# LTC3111_buck-boost.net
KiCad netlist of a schematic drawn in EAGLE
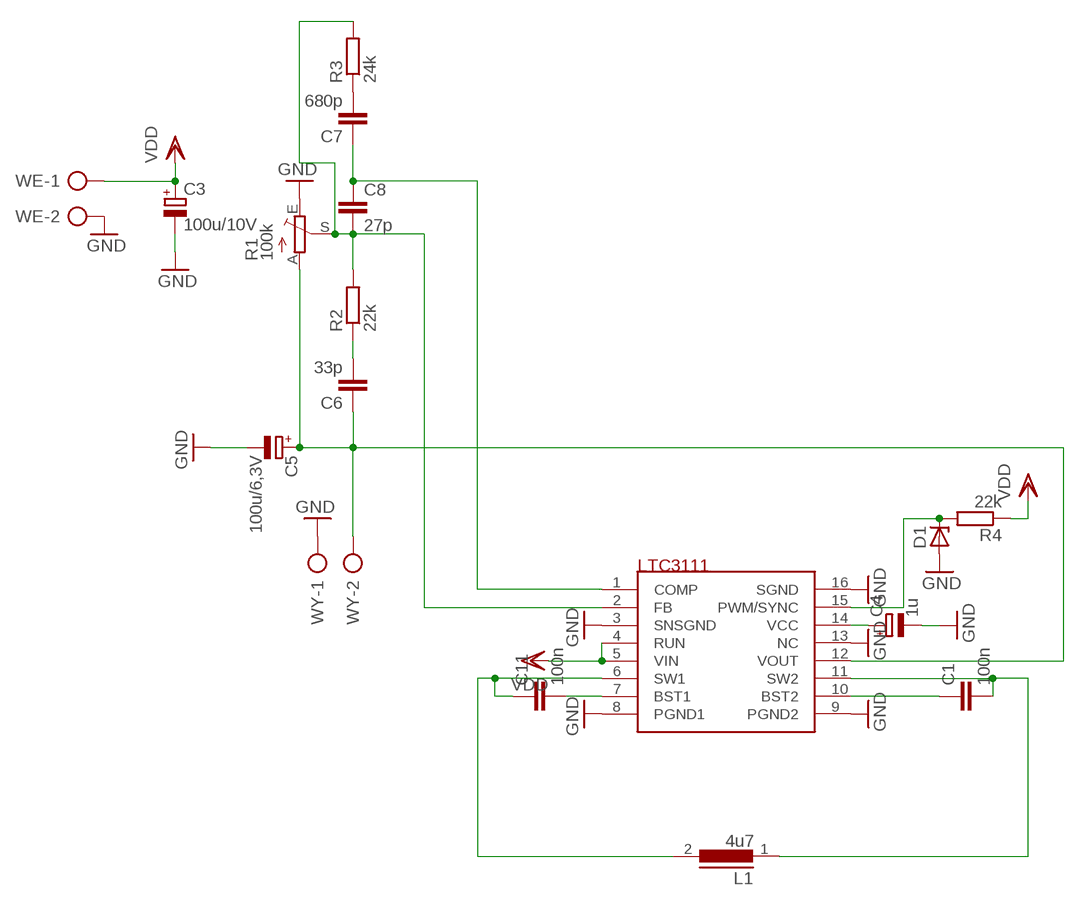
[diagram p0: schematic, sheet 1]

(export (version "E")
  (design (tool "Eeschema 10.0.6"))
  (components
    (comp (ref "C1")
      (value "100n")
      (footprint "eagle-import:C0603K")
      (libsource (lib "eagle-import") (part "C-EUC0603K"))
    )
    (comp (ref "C3")
      (value "100u/10V")
      (footprint "eagle-import:E2,5-6")
      (libsource (lib "eagle-import") (part "CPOL-EUE2.5-6"))
    )
    (comp (ref "C4")
      (value "1u")
      (footprint "eagle-import:E2,5-6")
      (libsource (lib "eagle-import") (part "CPOL-EUE2.5-6"))
    )
    (comp (ref "C5")
      (value "100u/6,3V")
      (footprint "eagle-import:E2,5-7")
      (libsource (lib "eagle-import") (part "CPOL-EUE2.5-7"))
    )
    (comp (ref "C6")
      (value "33p")
      (footprint "eagle-import:C0805")
      (libsource (lib "eagle-import") (part "C-EUC0805"))
    )
    (comp (ref "C7")
      (value "680p")
      (footprint "eagle-import:C0805")
      (libsource (lib "eagle-import") (part "C-EUC0805"))
    )
    (comp (ref "C8")
      (value "27p")
      (footprint "eagle-import:C0805")
      (libsource (lib "eagle-import") (part "C-EUC0805"))
    )
    (comp (ref "C11")
      (value "100n")
      (footprint "eagle-import:C0603K")
      (libsource (lib "eagle-import") (part "C-EUC0603K"))
    )
    (comp (ref "D1")
      (value "ZENER-DIODESOD80C")
      (footprint "eagle-import:SOD80C")
      (libsource (lib "eagle-import") (part "ZENER-DIODESOD80C"))
    )
    (comp (ref "L1")
      (value "4u7")
      (footprint "eagle-import:DR73")
      (libsource (lib "eagle-import") (part "DR73"))
    )
    (comp (ref "R1")
      (value "100k")
      (footprint "eagle-import:RJ9W")
      (libsource (lib "eagle-import") (part "TRIM_EU-RJ9W"))
    )
    (comp (ref "R2")
      (value "22k")
      (footprint "eagle-import:R0805")
      (libsource (lib "eagle-import") (part "R-EU_R0805"))
    )
    (comp (ref "R3")
      (value "24k")
      (footprint "eagle-import:R0805")
      (libsource (lib "eagle-import") (part "R-EU_R0805"))
    )
    (comp (ref "R4")
      (value "22k")
      (footprint "eagle-import:R0805")
      (libsource (lib "eagle-import") (part "R-EU_R0805"))
    )
    (comp (ref "U$2")
      (value "LTC3111")
      (footprint "eagle-import:MSOP16")
      (libsource (lib "eagle-import") (part "LTC3111"))
    )
    (comp (ref "WE")
      (value "AK300/2")
      (footprint "eagle-import:AK300_2")
      (libsource (lib "eagle-import") (part "AK300/2"))
    )
    (comp (ref "WY")
      (value "AK300/2")
      (footprint "eagle-import:AK300_2")
      (libsource (lib "eagle-import") (part "AK300/2"))
    )
  )
  (nets
    (net (code "1") (name "GND") (class "Default")
      (node (ref "C3") (pin "-") (pinfunction "-_-") (pintype "passive"))
      (node (ref "C4") (pin "-") (pinfunction "-_-") (pintype "passive"))
      (node (ref "C5") (pin "-") (pinfunction "-_-") (pintype "passive"))
      (node (ref "D1") (pin "A") (pinfunction "A_A") (pintype "passive"))
      (node (ref "R1") (pin "E") (pinfunction "E_E") (pintype "passive"))
      (node (ref "U$2") (pin "13") (pinfunction "NC_13") (pintype "bidirectional"))
      (node (ref "U$2") (pin "16") (pinfunction "SGND_16") (pintype "bidirectional"))
      (node (ref "U$2") (pin "3") (pinfunction "SNSGND_3") (pintype "bidirectional"))
      (node (ref "U$2") (pin "8") (pinfunction "PGND1_8") (pintype "bidirectional"))
      (node (ref "U$2") (pin "9") (pinfunction "PGND2_9") (pintype "bidirectional"))
      (node (ref "WE") (pin "2") (pinfunction "KL_2") (pintype "passive"))
      (node (ref "WY") (pin "1") (pinfunction "KL_1") (pintype "passive"))
    )
    (net (code "2") (name "Net-(C6-Pad2)") (class "Default")
      (node (ref "C6") (pin "2") (pinfunction "2_2") (pintype "passive"))
      (node (ref "R2") (pin "1") (pinfunction "1_1") (pintype "passive"))
    )
    (net (code "3") (name "Net-(C7-Pad2)") (class "Default")
      (node (ref "C7") (pin "2") (pinfunction "2_2") (pintype "passive"))
      (node (ref "R3") (pin "1") (pinfunction "1_1") (pintype "passive"))
    )
    (net (code "4") (name "Net-(U$2-BST1)") (class "Default")
      (node (ref "C11") (pin "2") (pinfunction "2_2") (pintype "passive"))
      (node (ref "U$2") (pin "7") (pinfunction "BST1_7") (pintype "bidirectional"))
    )
    (net (code "5") (name "Net-(U$2-BST2)") (class "Default")
      (node (ref "C1") (pin "1") (pinfunction "1_1") (pintype "passive"))
      (node (ref "U$2") (pin "10") (pinfunction "BST2_10") (pintype "bidirectional"))
    )
    (net (code "6") (name "Net-(U$2-COMP)") (class "Default")
      (node (ref "C7") (pin "1") (pinfunction "1_1") (pintype "passive"))
      (node (ref "C8") (pin "1") (pinfunction "1_1") (pintype "passive"))
      (node (ref "U$2") (pin "1") (pinfunction "COMP_1") (pintype "bidirectional"))
    )
    (net (code "7") (name "Net-(U$2-FB)") (class "Default")
      (node (ref "C8") (pin "2") (pinfunction "2_2") (pintype "passive"))
      (node (ref "R1") (pin "S") (pinfunction "S_S") (pintype "passive"))
      (node (ref "R2") (pin "2") (pinfunction "2_2") (pintype "passive"))
      (node (ref "R3") (pin "2") (pinfunction "2_2") (pintype "passive"))
      (node (ref "U$2") (pin "2") (pinfunction "FB_2") (pintype "bidirectional"))
    )
    (net (code "8") (name "Net-(U$2-PWM{slash}SYNC)") (class "Default")
      (node (ref "D1") (pin "C") (pinfunction "C_C") (pintype "passive"))
      (node (ref "R4") (pin "2") (pinfunction "2_2") (pintype "passive"))
      (node (ref "U$2") (pin "15") (pinfunction "PWM/SYNC_15") (pintype "bidirectional"))
    )
    (net (code "9") (name "Net-(U$2-SW1)") (class "Default")
      (node (ref "C11") (pin "1") (pinfunction "1_1") (pintype "passive"))
      (node (ref "L1") (pin "2") (pinfunction "2_2") (pintype "passive"))
      (node (ref "U$2") (pin "6") (pinfunction "SW1_6") (pintype "bidirectional"))
    )
    (net (code "10") (name "Net-(U$2-SW2)") (class "Default")
      (node (ref "C1") (pin "2") (pinfunction "2_2") (pintype "passive"))
      (node (ref "L1") (pin "1") (pinfunction "1_1") (pintype "passive"))
      (node (ref "U$2") (pin "11") (pinfunction "SW2_11") (pintype "bidirectional"))
    )
    (net (code "11") (name "Net-(U$2-VCC)") (class "Default")
      (node (ref "C4") (pin "+") (pinfunction "+_+") (pintype "passive"))
      (node (ref "U$2") (pin "14") (pinfunction "VCC_14") (pintype "bidirectional"))
    )
    (net (code "12") (name "Net-(U$2-VOUT)") (class "Default")
      (node (ref "C5") (pin "+") (pinfunction "+_+") (pintype "passive"))
      (node (ref "C6") (pin "1") (pinfunction "1_1") (pintype "passive"))
      (node (ref "R1") (pin "A") (pinfunction "A_A") (pintype "passive"))
      (node (ref "U$2") (pin "12") (pinfunction "VOUT_12") (pintype "bidirectional"))
      (node (ref "WY") (pin "2") (pinfunction "KL_2") (pintype "passive"))
    )
    (net (code "13") (name "VDD") (class "Default")
      (node (ref "C3") (pin "+") (pinfunction "+_+") (pintype "passive"))
      (node (ref "R4") (pin "1") (pinfunction "1_1") (pintype "passive"))
      (node (ref "U$2") (pin "4") (pinfunction "RUN_4") (pintype "bidirectional"))
      (node (ref "U$2") (pin "5") (pinfunction "VIN_5") (pintype "bidirectional"))
      (node (ref "WE") (pin "1") (pinfunction "KL_1") (pintype "passive"))
    )
  )
)
